# drive_pdu.net
KiCad netlist of a schematic drawn in EAGLE
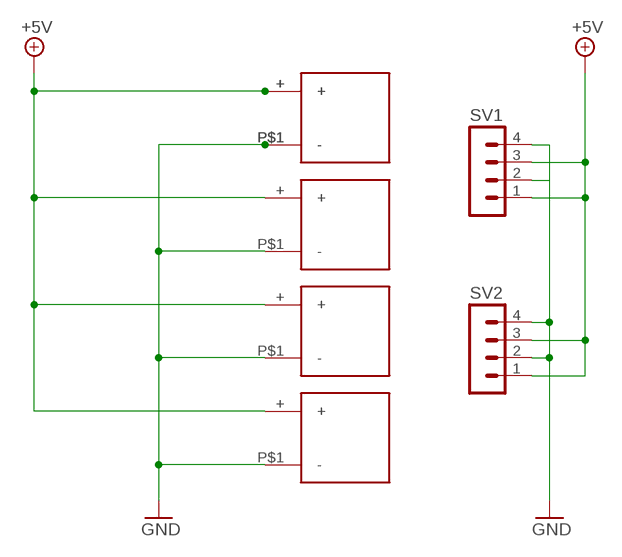
[diagram p0: schematic, sheet 1]

(export (version "E")
  (design (tool "Eeschema 10.0.6"))
  (components
    (comp (ref "SV1")
      (value "MA04-1")
      (footprint "eagle-import:MA04-1")
      (libsource (lib "eagle-import") (part "MA04-1"))
    )
    (comp (ref "SV2")
      (value "MA04-1")
      (footprint "eagle-import:MA04-1")
      (libsource (lib "eagle-import") (part "MA04-1"))
    )
    (comp (ref "U$1")
      (value "PP45-DG")
      (footprint "eagle-import:PP45-DG")
      (libsource (lib "eagle-import") (part "PP45-DG"))
    )
    (comp (ref "U$2")
      (value "PP45-DG")
      (footprint "eagle-import:PP45-DG")
      (libsource (lib "eagle-import") (part "PP45-DG"))
    )
    (comp (ref "U$3")
      (value "PP45-DG")
      (footprint "eagle-import:PP45-DG")
      (libsource (lib "eagle-import") (part "PP45-DG"))
    )
    (comp (ref "U$4")
      (value "PP45-DG")
      (footprint "eagle-import:PP45-DG")
      (libsource (lib "eagle-import") (part "PP45-DG"))
    )
    (comp (ref "U$5")
      (value "PP45-DG")
      (footprint "eagle-import:PP45-DG")
      (libsource (lib "eagle-import") (part "PP45-DG"))
    )
  )
  (nets
    (net (code "1") (name "+5V") (class "Default")
      (node (ref "SV1") (pin "1") (pinfunction "1_1") (pintype "passive"))
      (node (ref "SV1") (pin "3") (pinfunction "3_3") (pintype "passive"))
      (node (ref "SV2") (pin "1") (pinfunction "1_1") (pintype "passive"))
      (node (ref "SV2") (pin "3") (pinfunction "3_3") (pintype "passive"))
      (node (ref "U$1") (pin "+") (pinfunction "+_+") (pintype "bidirectional"))
      (node (ref "U$2") (pin "+") (pinfunction "+_+") (pintype "bidirectional"))
      (node (ref "U$3") (pin "+") (pinfunction "+_+") (pintype "bidirectional"))
      (node (ref "U$4") (pin "+") (pinfunction "+_+") (pintype "bidirectional"))
      (node (ref "U$5") (pin "+") (pinfunction "+_+") (pintype "bidirectional"))
    )
    (net (code "2") (name "GND") (class "Default")
      (node (ref "SV1") (pin "2") (pinfunction "2_2") (pintype "passive"))
      (node (ref "SV1") (pin "4") (pinfunction "4_4") (pintype "passive"))
      (node (ref "SV2") (pin "2") (pinfunction "2_2") (pintype "passive"))
      (node (ref "SV2") (pin "4") (pinfunction "4_4") (pintype "passive"))
      (node (ref "U$1") (pin "P$1") (pinfunction "-_P$1") (pintype "bidirectional"))
      (node (ref "U$2") (pin "P$1") (pinfunction "-_P$1") (pintype "bidirectional"))
      (node (ref "U$3") (pin "P$1") (pinfunction "-_P$1") (pintype "bidirectional"))
      (node (ref "U$4") (pin "P$1") (pinfunction "-_P$1") (pintype "bidirectional"))
      (node (ref "U$5") (pin "P$1") (pinfunction "-_P$1") (pintype "bidirectional"))
    )
  )
)
